# aeroponics_schematic.net
KiCad netlist of a schematic drawn in EasyEDA
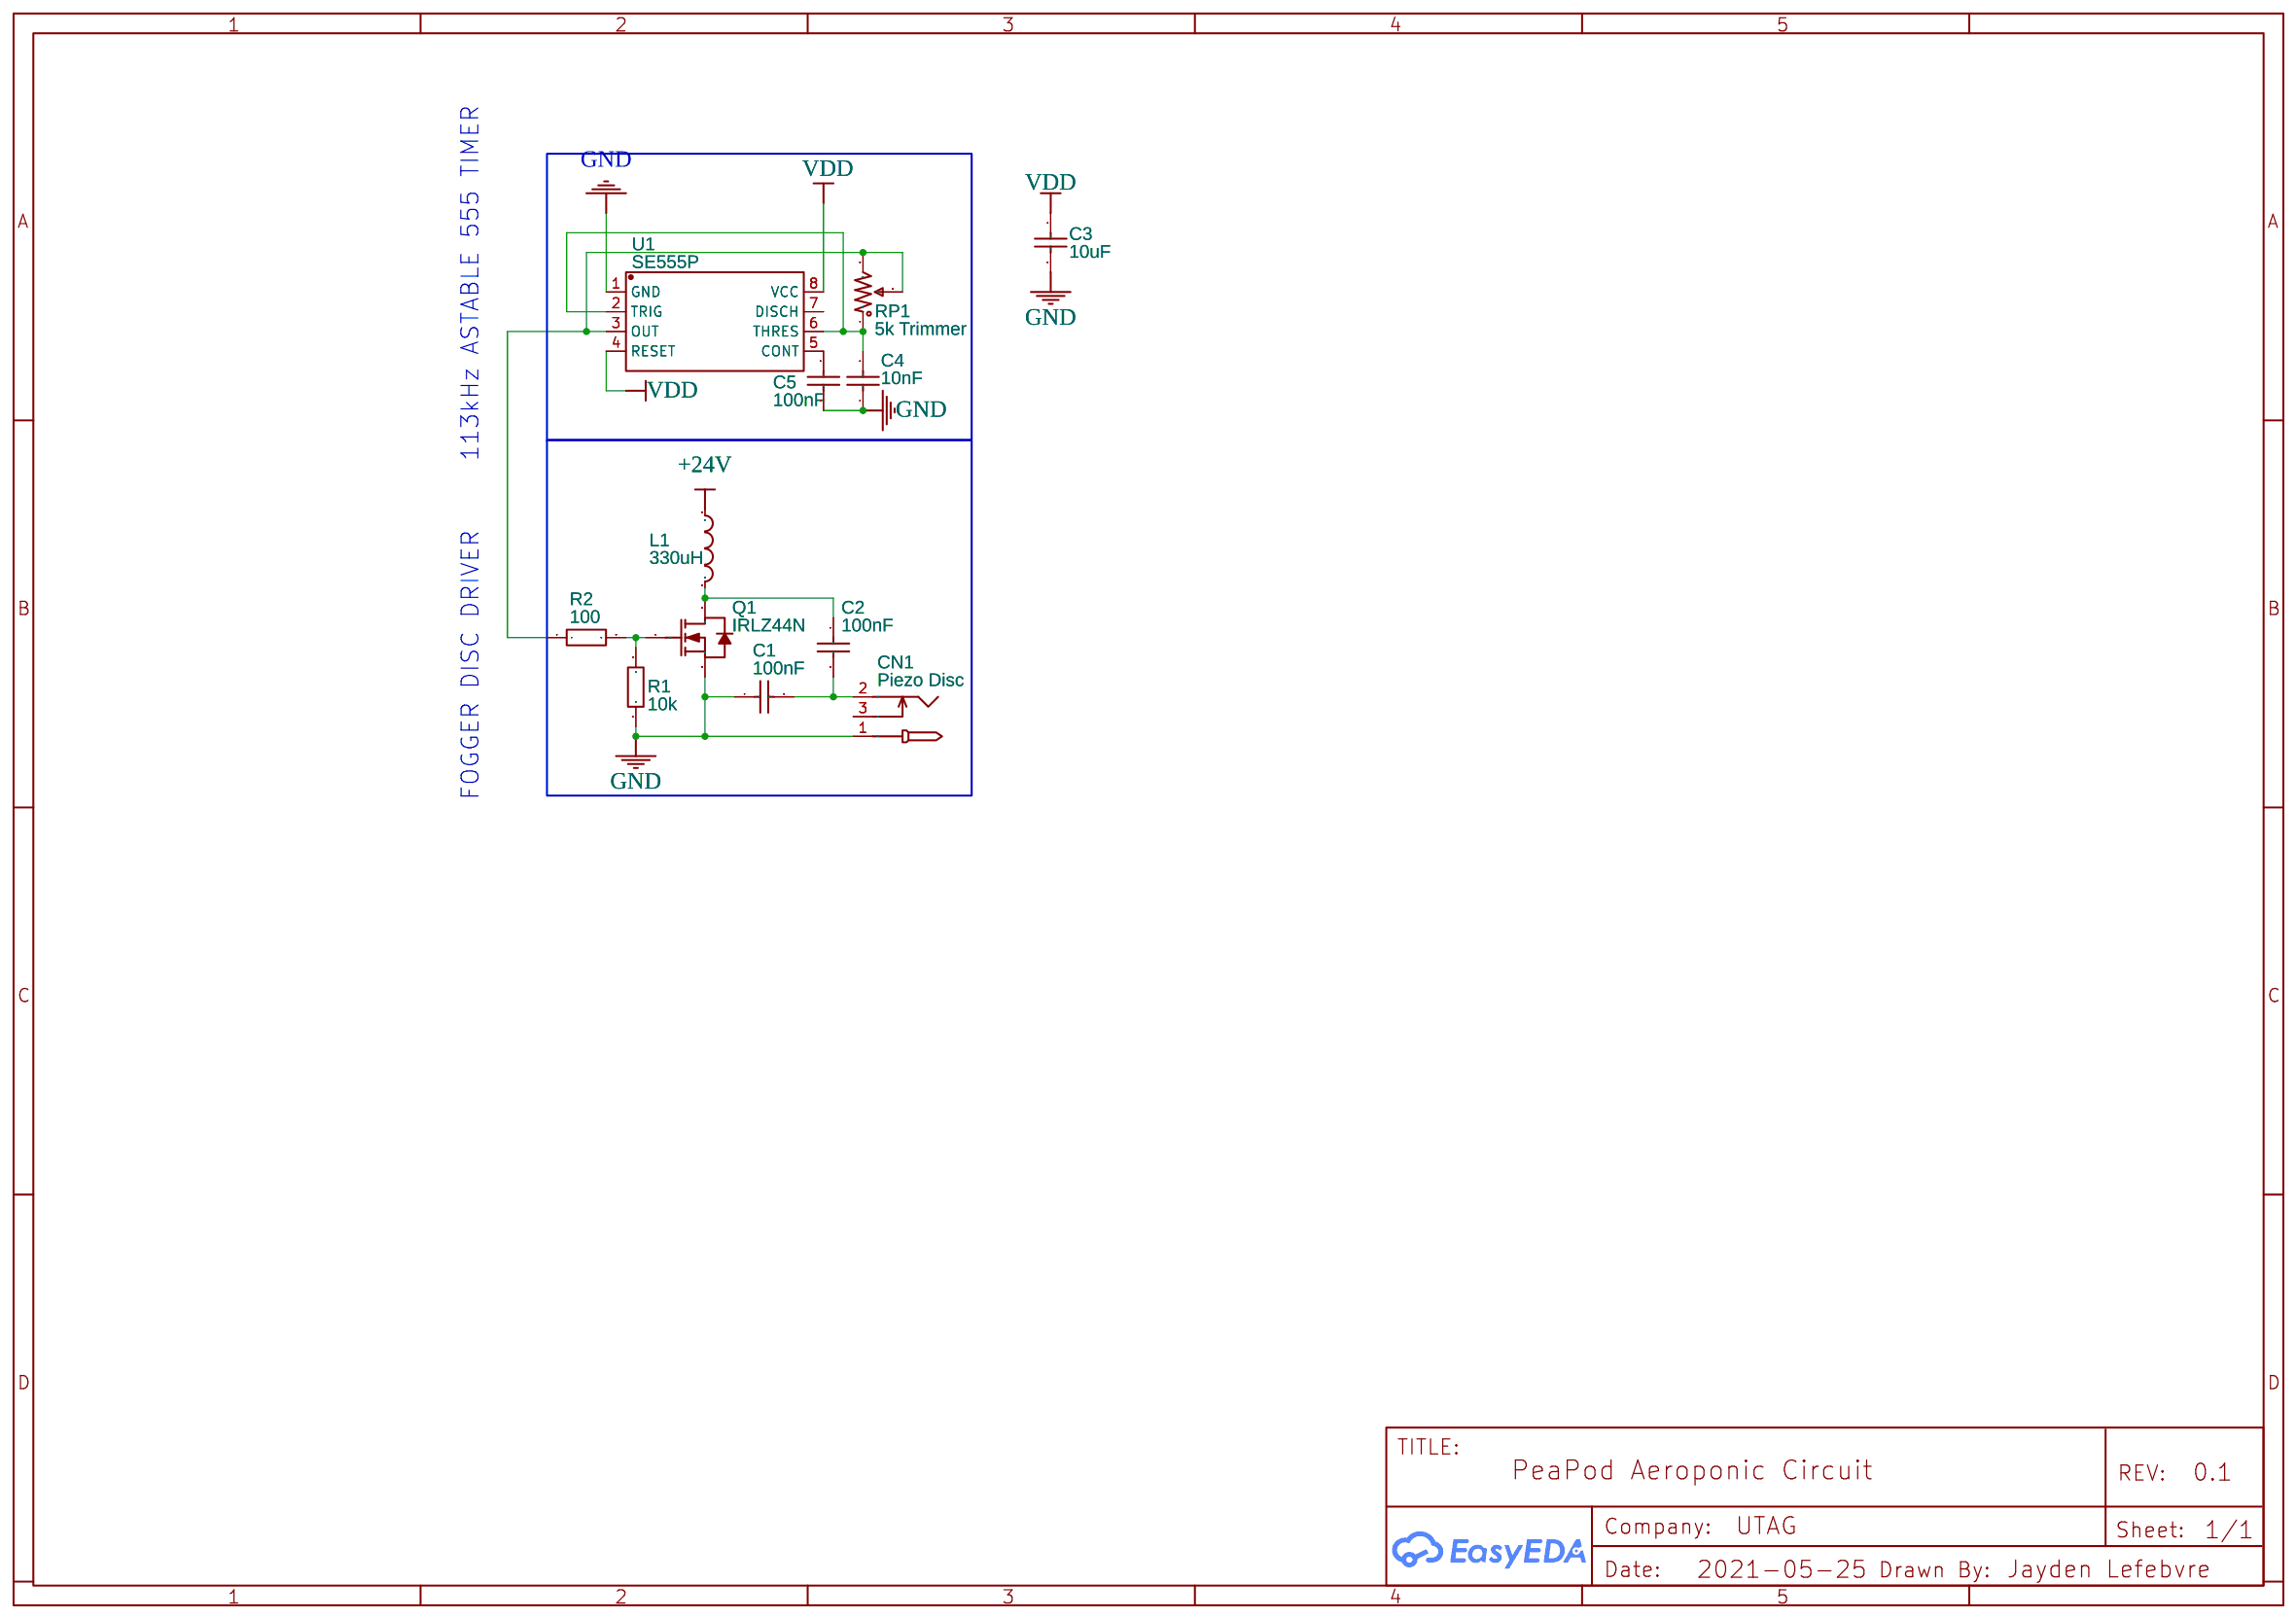
[diagram p0: schematic sheet]

(export (version "E")
  (design (tool "Eeschema 10.0.6"))
  (components
    (comp (ref "C1")
      (value "100nF")
      (fields
        (field (name "BOM_Manufacturer Part") "CL05A106MQ5NUNC")
        (field (name "BOM_Supplier Part") "C15525")
      )
      (libsource (lib "") (part "CL05A106MQ5NUNC_1"))
    )
    (comp (ref "C2")
      (value "100nF")
      (fields
        (field (name "BOM_Manufacturer Part") "CL05A106MQ5NUNC")
        (field (name "BOM_Supplier Part") "C15525")
      )
      (libsource (lib "") (part "CL05A106MQ5NUNC_2"))
    )
    (comp (ref "C3")
      (value "10uF")
      (fields
        (field (name "BOM_Manufacturer Part") "CL05A106MQ5NUNC")
        (field (name "BOM_Supplier Part") "C15525")
      )
      (libsource (lib "") (part "CL05A106MQ5NUNC_2"))
    )
    (comp (ref "C4")
      (value "10nF")
      (fields
        (field (name "BOM_Manufacturer Part") "CL05A106MQ5NUNC")
        (field (name "BOM_Supplier Part") "C15525")
      )
      (libsource (lib "") (part "CL05A106MQ5NUNC"))
    )
    (comp (ref "C5")
      (value "100nF")
      (fields
        (field (name "BOM_Manufacturer Part") "CL05A106MQ5NUNC")
        (field (name "BOM_Supplier Part") "C15525")
      )
      (libsource (lib "") (part "CL05A106MQ5NUNC"))
    )
    (comp (ref "CN1")
      (value "Piezo Disc")
      (fields
        (field (name "BOM_Manufacturer Part") "DC005-2.0MM")
        (field (name "BOM_Supplier Part") "C111567")
      )
      (libsource (lib "") (part "DC005-2.0MM"))
    )
    (comp (ref "L1") (value "330uH") (libsource (lib "") (part "L0402_US")))
    (comp (ref "Q1")
      (value "IRLZ44N")
      (fields (field (name "BOM_Manufacturer Part") "IRLZ44NPBF") (field (name "BOM_Supplier Part") "C38774"))
      (libsource (lib "") (part "IRLZ44NPBF"))
    )
    (comp (ref "R1")
      (value "10k")
      (fields
        (field (name "BOM_Manufacturer Part") "0402WGF4751TCE")
        (field (name "BOM_Supplier Part") "C25901")
      )
      (libsource (lib "") (part "0402WGF4751TCE"))
    )
    (comp (ref "R2")
      (value "100")
      (fields
        (field (name "BOM_Manufacturer Part") "0402WGF4751TCE")
        (field (name "BOM_Supplier Part") "C25901")
      )
      (libsource (lib "") (part "0402WGF4751TCE_1"))
    )
    (comp (ref "RP1") (value "5k Trimmer") (libsource (lib "") (part "R_3386P_US")))
    (comp (ref "U1")
      (value "SE555P")
      (fields (field (name "BOM_Manufacturer Part") "NE555D") (field (name "BOM_Supplier Part") "C234230"))
      (libsource (lib "") (part "NE555D"))
    )
  )
  (nets
    (net (code "1") (name "+24V") (class "Default")
      (node (ref "L1") (pin "1") (pinfunction "1_1") (pintype "unspecified"))
    )
    (net (code "2") (name "GND") (class "Default")
      (node (ref "C1") (pin "1") (pinfunction "1_1") (pintype "input"))
      (node (ref "C3") (pin "2") (pinfunction "2_2") (pintype "input"))
      (node (ref "C4") (pin "1") (pinfunction "1_1") (pintype "input"))
      (node (ref "C5") (pin "1") (pinfunction "1_1") (pintype "input"))
      (node (ref "CN1") (pin "1") (pinfunction "1_1") (pintype "unspecified"))
      (node (ref "Q1") (pin "3") (pinfunction "S_3") (pintype "unspecified"))
      (node (ref "R1") (pin "1") (pinfunction "1_1") (pintype "input"))
      (node (ref "U1") (pin "1") (pinfunction "GND_1") (pintype "unspecified"))
    )
    (net (code "3") (name "Net-(C1-Pad2)") (class "Default")
      (node (ref "C1") (pin "2") (pinfunction "2_2") (pintype "input"))
      (node (ref "C2") (pin "2") (pinfunction "2_2") (pintype "input"))
      (node (ref "CN1") (pin "2") (pinfunction "2_2") (pintype "unspecified"))
    )
    (net (code "4") (name "Net-(Q1-D)") (class "Default")
      (node (ref "C2") (pin "1") (pinfunction "1_1") (pintype "input"))
      (node (ref "L1") (pin "2") (pinfunction "2_2") (pintype "unspecified"))
      (node (ref "Q1") (pin "2") (pinfunction "D_2") (pintype "unspecified"))
    )
    (net (code "5") (name "Net-(Q1-G)") (class "Default")
      (node (ref "Q1") (pin "1") (pinfunction "G_1") (pintype "unspecified"))
      (node (ref "R1") (pin "2") (pinfunction "2_2") (pintype "input"))
      (node (ref "R2") (pin "2") (pinfunction "2_2") (pintype "input"))
    )
    (net (code "6") (name "Net-(U1-CONT)") (class "Default")
      (node (ref "C5") (pin "2") (pinfunction "2_2") (pintype "input"))
      (node (ref "U1") (pin "5") (pinfunction "CONT_5") (pintype "unspecified"))
    )
    (net (code "7") (name "Net-(U1-OUT)") (class "Default")
      (node (ref "R2") (pin "1") (pinfunction "1_1") (pintype "input"))
      (node (ref "RP1") (pin "2") (pinfunction "2_2") (pintype "unspecified"))
      (node (ref "RP1") (pin "3") (pinfunction "3_3") (pintype "unspecified"))
      (node (ref "U1") (pin "3") (pinfunction "OUT_3") (pintype "unspecified"))
    )
    (net (code "8") (name "Net-(U1-THRES)") (class "Default")
      (node (ref "C4") (pin "2") (pinfunction "2_2") (pintype "input"))
      (node (ref "RP1") (pin "1") (pinfunction "1_1") (pintype "unspecified"))
      (node (ref "U1") (pin "2") (pinfunction "TRIG_2") (pintype "unspecified"))
      (node (ref "U1") (pin "6") (pinfunction "THRES_6") (pintype "unspecified"))
    )
    (net (code "9") (name "VDD") (class "Default")
      (node (ref "C3") (pin "1") (pinfunction "1_1") (pintype "input"))
      (node (ref "U1") (pin "4") (pinfunction "RESET_4") (pintype "unspecified"))
      (node (ref "U1") (pin "8") (pinfunction "VCC_8") (pintype "unspecified"))
    )
    (net (code "10") (name "unconnected-(CN1-Pad3)") (class "Default")
      (node (ref "CN1") (pin "3") (pinfunction "3_3") (pintype "unspecified"))
    )
    (net (code "11") (name "unconnected-(U1-DISCH-Pad7)") (class "Default")
      (node (ref "U1") (pin "7") (pinfunction "DISCH_7") (pintype "unspecified"))
    )
  )
)
